# ESP32-S2-Ink.net
KiCad netlist of a schematic drawn in Altium Designer
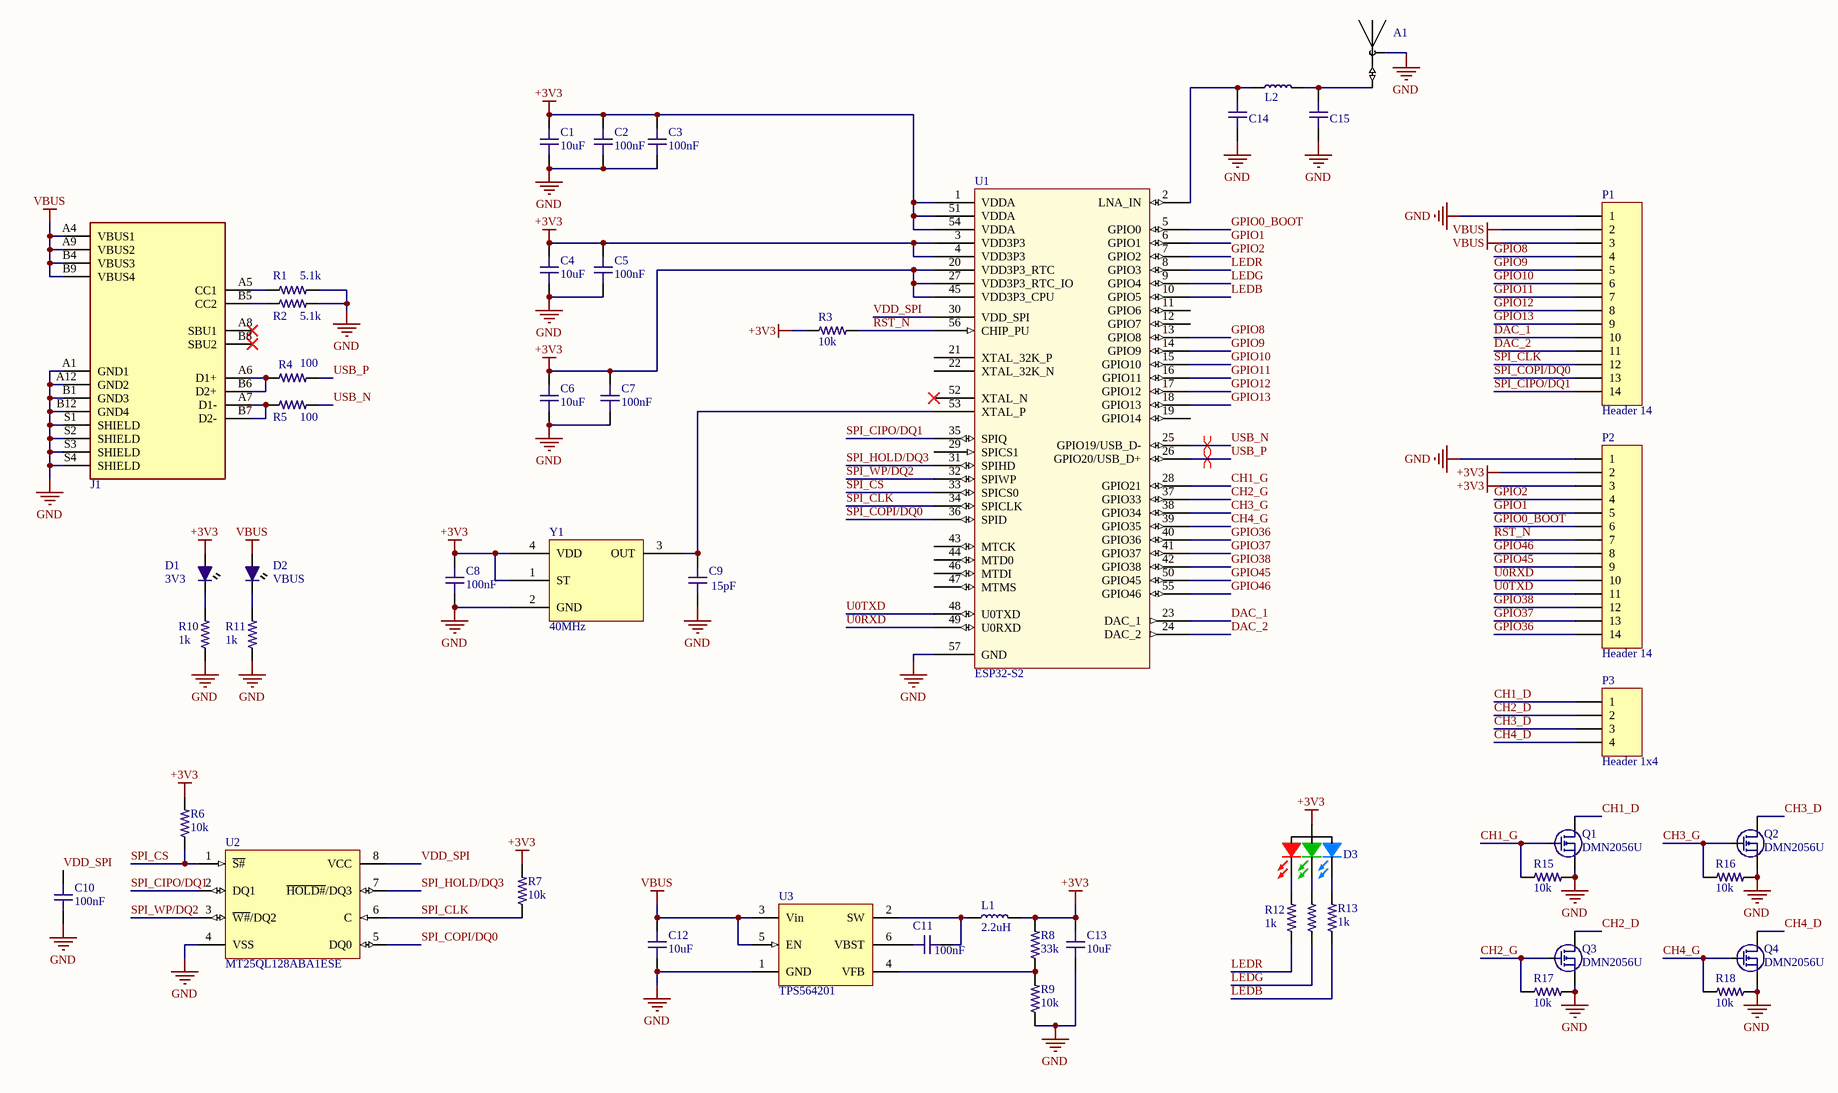
[diagram p0: ESP32-S2-Ink.SchDoc]

(export (version "E")
  (design (tool "Eeschema 10.0.6"))
  (components
    (comp (ref "A1")
      (value "0479480001")
      (footprint "0479480001")
      (description "2.4GHz Bluetooth, WLAN, Zigbee™ Chip RF Antenna 2.4GHz ~ 2.483.5GHz 3dBi Solder Surface Mount")
      (libsource (lib "RF Components") (part "Molex 0479480001"))
    )
    (comp (ref "C1")
      (value "10uF")
      (footprint "C0402-HIGH-DENSITY")
      (description "Chip Capacitor, 0402, 10uF, 10V, X5R")
      (fields (field (name "Comment") "C0402 10uF 10V"))
      (libsource (lib "Capacitors") (part "C0402 10uF 10V"))
    )
    (comp (ref "C2")
      (value "100nF")
      (footprint "C0402-HIGH-DENSITY")
      (description "Chip Capacitor, 0402, 100nF, 10V, X5R")
      (fields (field (name "Comment") "C0402 100nF 10V X5R"))
      (libsource (lib "Capacitors") (part "C0402 100nF 10V X5R"))
    )
    (comp (ref "C3")
      (value "100nF")
      (footprint "C0402-HIGH-DENSITY")
      (description "Chip Capacitor, 0402, 100nF, 10V, X5R")
      (fields (field (name "Comment") "C0402 100nF 10V X5R"))
      (libsource (lib "Capacitors") (part "C0402 100nF 10V X5R"))
    )
    (comp (ref "C4")
      (value "10uF")
      (footprint "C0402-HIGH-DENSITY")
      (description "Chip Capacitor, 0402, 10uF, 10V, X5R")
      (fields (field (name "Comment") "C0402 10uF 10V"))
      (libsource (lib "Capacitors") (part "C0402 10uF 10V"))
    )
    (comp (ref "C5")
      (value "100nF")
      (footprint "C0402-HIGH-DENSITY")
      (description "Chip Capacitor, 0402, 100nF, 10V, X5R")
      (fields (field (name "Comment") "C0402 100nF 10V X5R"))
      (libsource (lib "Capacitors") (part "C0402 100nF 10V X5R"))
    )
    (comp (ref "C6")
      (value "10uF")
      (footprint "C0402-HIGH-DENSITY")
      (description "Chip Capacitor, 0402, 10uF, 10V, X5R")
      (fields (field (name "Comment") "C0402 10uF 10V"))
      (libsource (lib "Capacitors") (part "C0402 10uF 10V"))
    )
    (comp (ref "C7")
      (value "100nF")
      (footprint "C0402-HIGH-DENSITY")
      (description "Chip Capacitor, 0402, 100nF, 10V, X5R")
      (fields (field (name "Comment") "C0402 100nF 10V X5R"))
      (libsource (lib "Capacitors") (part "C0402 100nF 10V X5R"))
    )
    (comp (ref "C8")
      (value "100nF")
      (footprint "C0402-HIGH-DENSITY")
      (description "Chip Capacitor, 0402, 100nF, 10V, X5R")
      (fields (field (name "Comment") "C0402 100nF 10V X5R"))
      (libsource (lib "Capacitors") (part "C0402 100nF 10V X5R"))
    )
    (comp (ref "C9")
      (value "15pF")
      (footprint "C0402-HIGH-DENSITY")
      (description "Chip Capacitor, 0402, 15pF, 50V, C0G")
      (fields (field (name "Comment") "C0402 15pF 50V C0G"))
      (libsource (lib "Capacitors") (part "C0402 16pF 50V C0G"))
    )
    (comp (ref "C10")
      (value "100nF")
      (footprint "C0402-HIGH-DENSITY")
      (description "Chip Capacitor, 0402, 100nF, 10V, X5R")
      (fields (field (name "Comment") "C0402 100nF 10V X5R"))
      (libsource (lib "Capacitors") (part "C0402 100nF 10V X5R"))
    )
    (comp (ref "C11")
      (value "100nF")
      (footprint "C0402-HIGH-DENSITY")
      (description "Chip Capacitor, 0402, 100nF, 10V, X5R")
      (fields (field (name "Comment") "C0402 100nF 10V X5R"))
      (libsource (lib "Capacitors") (part "C0402 100nF 10V X5R"))
    )
    (comp (ref "C12")
      (value "10uF")
      (footprint "C0402-HIGH-DENSITY")
      (description "Chip Capacitor, 0402, 10uF, 10V, X5R")
      (fields (field (name "Comment") "C0402 10uF 10V"))
      (libsource (lib "Capacitors") (part "C0402 10uF 10V"))
    )
    (comp (ref "C13")
      (value "10uF")
      (footprint "C0402-HIGH-DENSITY")
      (description "Chip Capacitor, 0402, 10uF, 10V, X5R")
      (fields (field (name "Comment") "C0402 10uF 10V"))
      (libsource (lib "Capacitors") (part "C0402 10uF 10V"))
    )
    (comp (ref "C14")
      (value "0402 Capacitor Template")
      (footprint "C0402-HIGH-DENSITY")
      (description "Chip Capacitor, 0402, ??nF, 10V, X7R")
      (libsource (lib "Capacitors") (part "0402 Capacitor Template"))
    )
    (comp (ref "C15")
      (value "0402 Capacitor Template")
      (footprint "C0402-HIGH-DENSITY")
      (description "Chip Capacitor, 0402, ??nF, 10V, X7R")
      (libsource (lib "Capacitors") (part "0402 Capacitor Template"))
    )
    (comp (ref "D1")
      (value "3V3")
      (footprint "LED0603-IPC")
      (description "LED YELLOW CLEAR 0603 SMD")
      (libsource (lib "Diodes") (part "LED 0603 Yellow"))
    )
    (comp (ref "D2")
      (value "VBUS")
      (footprint "LED0603-IPC")
      (description "LED YELLOW CLEAR 0603 SMD")
      (libsource (lib "Diodes") (part "LED 0603 Yellow"))
    )
    (comp (ref "D3")
      (value "RGB")
      (footprint "Diodes:LED_0606_RGB_WURTH")
      (description "RGB Led 1.6 x 1.6 mm Diffused")
      (fields
        (field (name "MANUFACTURER") "Everlight")
        (field (name "MANUFACTURER PART NUMBER") "19-237/R6GHBHW-C01/2T")
      )
      (libsource (lib "Diodes") (part "Led_RGB_0606"))
    )
    (comp (ref "J1")
      (value "16 Pin Mid Mount USB C")
      (footprint "USB-C - 16 Pin Mid Mount")
      (description "USB-C USB 2.0 5A PD 16 Position Mid Mount")
      (fields (field (name "MANUFACTURER") "Jing Extension of the Electronic Co"))
      (libsource (lib "Connectors") (part "USB C USB 2.0 and PD"))
    )
    (comp (ref "L1")
      (value "2.2uH")
      (footprint "L1008")
      (description "2.2µH Shielded Inductor 2.05A 117mOhm Max 1008 (2520 Metric)")
      (fields (field (name "Comment") "SDEM25201B-2R2MS"))
      (libsource (lib "Inductors") (part "SDEM25201B-2R2MS"))
    )
    (comp (ref "L2")
      (value "! Inductor Template")
      (footprint "L0402-Murata-WW-High-Density")
      (description "Inductor, ??uH")
      (libsource (lib "Inductors") (part "! Inductor Template"))
    )
    (comp (ref "P1")
      (value "Header 14")
      (footprint "HDR1X14")
      (description "Header, 14-Pin")
      (fields (field (name "PUBLISHER") "Altium Limited"))
      (libsource (lib "Miscellaneous Connectors") (part "Header 14"))
    )
    (comp (ref "P2")
      (value "Header 14")
      (footprint "HDR1X14")
      (description "Header, 14-Pin")
      (fields (field (name "PUBLISHER") "Altium Limited"))
      (libsource (lib "Miscellaneous Connectors") (part "Header 14"))
    )
    (comp (ref "P3")
      (value "Header 1x4")
      (footprint "HEADER 1X4 SMD 2.54mm")
      (description "Header, 4-Pin")
      (fields (field (name "PUBLISHER") "Altium Limited"))
      (libsource (lib "Connectors") (part "Header 1x4"))
    )
    (comp (ref "Q1")
      (value "DMN2056U")
      (footprint "SOT23-DMN2056")
      (description "MOSFET N-Ch -20V VDSS Enchanced Mosfet 4.2A")
      (libsource (lib "Transistors") (part "DMN2056U"))
    )
    (comp (ref "Q2")
      (value "DMN2056U")
      (footprint "SOT23-DMN2056")
      (description "MOSFET N-Ch -20V VDSS Enchanced Mosfet 4.2A")
      (libsource (lib "Transistors") (part "DMN2056U"))
    )
    (comp (ref "Q3")
      (value "DMN2056U")
      (footprint "SOT23-DMN2056")
      (description "MOSFET N-Ch -20V VDSS Enchanced Mosfet 4.2A")
      (libsource (lib "Transistors") (part "DMN2056U"))
    )
    (comp (ref "Q4")
      (value "DMN2056U")
      (footprint "SOT23-DMN2056")
      (description "MOSFET N-Ch -20V VDSS Enchanced Mosfet 4.2A")
      (libsource (lib "Transistors") (part "DMN2056U"))
    )
    (comp (ref "R1")
      (value "5.1k")
      (footprint "R0402-HIGH-DENSITY")
      (description "RES SMD 5.1K OHM 1% 1/10W 0402")
      (fields (field (name "Comment") "R0402 5.1K 1%"))
      (libsource (lib "Resistors") (part "R0402 5.1K 1%"))
    )
    (comp (ref "R2")
      (value "5.1k")
      (footprint "R0402-HIGH-DENSITY")
      (description "RES SMD 5.1K OHM 1% 1/10W 0402")
      (fields (field (name "Comment") "R0402 5.1K 1%"))
      (libsource (lib "Resistors") (part "R0402 5.1K 1%"))
    )
    (comp (ref "R3")
      (value "10k")
      (footprint "R0402-HIGH-DENSITY")
      (description "Chip Resistor, 0402, 10k ohms, 1%, 1/16 W")
      (fields (field (name "Comment") "R0402 10k 1%"))
      (libsource (lib "Resistors") (part "R0402 10k 1%"))
    )
    (comp (ref "R4")
      (value "100")
      (footprint "R0402-HIGH-DENSITY")
      (description "Chip Resistor, 0402, 100 ohms, 1%, 1/16 W")
      (fields (field (name "Comment") "R0402 100R 1%"))
      (libsource (lib "Resistors") (part "R0402 100R 1%"))
    )
    (comp (ref "R5")
      (value "100")
      (footprint "R0402-HIGH-DENSITY")
      (description "Chip Resistor, 0402, 100 ohms, 1%, 1/16 W")
      (fields (field (name "Comment") "R0402 100R 1%"))
      (libsource (lib "Resistors") (part "R0402 100R 1%"))
    )
    (comp (ref "R6")
      (value "10k")
      (footprint "R0402-HIGH-DENSITY")
      (description "Chip Resistor, 0402, 10k ohms, 1%, 1/16 W")
      (fields (field (name "Comment") "R0402 10k 1%"))
      (libsource (lib "Resistors") (part "R0402 10k 1%"))
    )
    (comp (ref "R7")
      (value "10k")
      (footprint "R0402-HIGH-DENSITY")
      (description "Chip Resistor, 0402, 10k ohms, 1%, 1/16 W")
      (fields (field (name "Comment") "R0402 10k 1%"))
      (libsource (lib "Resistors") (part "R0402 10k 1%"))
    )
    (comp (ref "R8")
      (value "33k")
      (footprint "R0402-HIGH-DENSITY")
      (description "Chip Resistor, 0402, 33k ohms, 1%, 1/16 W")
      (fields (field (name "Comment") "R0402 33k 1%"))
      (libsource (lib "Resistors") (part "R0402 33k 1%"))
    )
    (comp (ref "R9")
      (value "10k")
      (footprint "R0402-HIGH-DENSITY")
      (description "Chip Resistor, 0402, 10k ohms, 1%, 1/16 W")
      (fields (field (name "Comment") "R0402 10k 1%"))
      (libsource (lib "Resistors") (part "R0402 10k 1%"))
    )
    (comp (ref "R10")
      (value "1k")
      (footprint "R0402-HIGH-DENSITY")
      (description "Chip Resistor, 0402, 1k ohms, 1%, 1/16 W")
      (fields (field (name "Comment") "R0402 1k 1%"))
      (libsource (lib "Resistors") (part "R0402 1k 1%"))
    )
    (comp (ref "R11")
      (value "1k")
      (footprint "R0402-HIGH-DENSITY")
      (description "Chip Resistor, 0402, 1k ohms, 1%, 1/16 W")
      (fields (field (name "Comment") "R0402 1k 1%"))
      (libsource (lib "Resistors") (part "R0402 1k 1%"))
    )
    (comp (ref "R12")
      (value "1k")
      (footprint "R0402-HIGH-DENSITY")
      (description "Chip Resistor, 0402, 1k ohms, 1%, 1/16 W")
      (fields (field (name "Comment") "R0402 1k 1%"))
      (libsource (lib "Resistors") (part "R0402 1k 1%"))
    )
    (comp (ref "R13")
      (value "1k")
      (footprint "R0402-HIGH-DENSITY")
      (description "Chip Resistor, 0402, 1k ohms, 1%, 1/16 W")
      (fields (field (name "Comment") "R0402 1k 1%"))
      (libsource (lib "Resistors") (part "R0402 1k 1%"))
    )
    (comp (ref "R14")
      (value "R0402 1k 1%")
      (footprint "R0402-HIGH-DENSITY")
      (description "Chip Resistor, 0402, 1k ohms, 1%, 1/16 W")
      (libsource (lib "Resistors") (part "R0402 1k 1%"))
    )
    (comp (ref "R15")
      (value "10k")
      (footprint "R0402-HIGH-DENSITY")
      (description "Chip Resistor, 0402, 10k ohms, 1%, 1/16 W")
      (fields (field (name "Comment") "R0402 10k 1%"))
      (libsource (lib "Resistors") (part "R0402 10k 1%"))
    )
    (comp (ref "R16")
      (value "10k")
      (footprint "R0402-HIGH-DENSITY")
      (description "Chip Resistor, 0402, 10k ohms, 1%, 1/16 W")
      (fields (field (name "Comment") "R0402 10k 1%"))
      (libsource (lib "Resistors") (part "R0402 10k 1%"))
    )
    (comp (ref "R17")
      (value "10k")
      (footprint "R0402-HIGH-DENSITY")
      (description "Chip Resistor, 0402, 10k ohms, 1%, 1/16 W")
      (fields (field (name "Comment") "R0402 10k 1%"))
      (libsource (lib "Resistors") (part "R0402 10k 1%"))
    )
    (comp (ref "R18")
      (value "10k")
      (footprint "R0402-HIGH-DENSITY")
      (description "Chip Resistor, 0402, 10k ohms, 1%, 1/16 W")
      (fields (field (name "Comment") "R0402 10k 1%"))
      (libsource (lib "Resistors") (part "R0402 10k 1%"))
    )
    (comp (ref "U1")
      (value "ESP32-S2")
      (footprint "QFN56")
      (description "WiFi 802.11b/g/n Transceiver Module 2.4GHz QFN-56")
      (libsource (lib "Integrated Circuits") (part "ESP32-S2"))
    )
    (comp (ref "U2")
      (value "MT25QL128ABA1ESE")
      (footprint "SOIC127P800X216-8N")
      (description "SPI Flash, 128Mb, 3V")
      (libsource (lib "Integrated Circuits") (part "MT25QL128ABA1ESE"))
    )
    (comp (ref "U3")
      (value "TPS564201")
      (footprint "SOT95P280X90-6N")
      (description "Buck Converter, 4.5-17V in, 0.76-7V out, 4A, TSOT-6")
      (fields
        (field (name "MANUFACTURER") "Texas Instruments")
        (field (name "LAST MODIFIED BY") "Peter Kazakoff")
      )
      (libsource (lib "Integrated Circuits") (part "TPS564201"))
    )
    (comp (ref "Y1")
      (value "40MHz")
      (footprint "SiT8008B")
      (description "OSC MEMS 40.0000MHZ 1.8-3.3V 2016 SMD 15pF Load")
      (libsource (lib "RF Components") (part "40MHZ CMOS ±10ppm"))
    )
  )
  (nets
    (net (code "1") (name "+3V3") (class "Default")
      (node (ref "C1") (pin "2") (pintype "passive"))
      (node (ref "C13") (pin "2") (pintype "passive"))
      (node (ref "C2") (pin "2") (pintype "passive"))
      (node (ref "C3") (pin "2") (pintype "passive"))
      (node (ref "C4") (pin "2") (pintype "passive"))
      (node (ref "C5") (pin "2") (pintype "passive"))
      (node (ref "C6") (pin "2") (pintype "passive"))
      (node (ref "C7") (pin "2") (pintype "passive"))
      (node (ref "C8") (pin "2") (pintype "passive"))
      (node (ref "D1") (pin "A") (pintype "passive"))
      (node (ref "D3") (pin "A") (pinfunction "A_A") (pintype "passive"))
      (node (ref "L1") (pin "2") (pintype "passive"))
      (node (ref "P2") (pin "2") (pinfunction "2_2") (pintype "passive"))
      (node (ref "P2") (pin "3") (pinfunction "3_3") (pintype "passive"))
      (node (ref "R3") (pin "1") (pintype "passive"))
      (node (ref "R6") (pin "1") (pintype "passive"))
      (node (ref "R7") (pin "1") (pintype "passive"))
      (node (ref "R8") (pin "2") (pintype "passive"))
      (node (ref "U1") (pin "1") (pinfunction "VDDA_1") (pintype "power_in"))
      (node (ref "U1") (pin "20") (pinfunction "VDD3P3_RTC_20") (pintype "power_in"))
      (node (ref "U1") (pin "27") (pinfunction "VDD3P3_RTC_IO_27") (pintype "power_in"))
      (node (ref "U1") (pin "3") (pinfunction "VDD3P3_3") (pintype "power_in"))
      (node (ref "U1") (pin "4") (pinfunction "VDD3P3_4") (pintype "power_in"))
      (node (ref "U1") (pin "45") (pinfunction "VDD3P3_CPU_45") (pintype "power_in"))
      (node (ref "U1") (pin "51") (pinfunction "VDDA_51") (pintype "power_in"))
      (node (ref "U1") (pin "54") (pinfunction "VDDA_54") (pintype "power_in"))
      (node (ref "Y1") (pin "1") (pinfunction "ST_1") (pintype "passive"))
      (node (ref "Y1") (pin "4") (pinfunction "VDD_4") (pintype "passive"))
    )
    (net (code "2") (name "/CH1_D") (class "Default")
      (node (ref "P3") (pin "1") (pinfunction "1_1") (pintype "passive"))
      (node (ref "Q1") (pin "3") (pinfunction "D_3") (pintype "passive"))
    )
    (net (code "3") (name "/CH1_G") (class "Default")
      (node (ref "Q1") (pin "1") (pinfunction "G_1") (pintype "passive"))
      (node (ref "R15") (pin "2") (pintype "passive"))
      (node (ref "U1") (pin "28") (pinfunction "GPIO21_28") (pintype "bidirectional"))
    )
    (net (code "4") (name "/CH2_D") (class "Default")
      (node (ref "P3") (pin "2") (pinfunction "2_2") (pintype "passive"))
      (node (ref "Q3") (pin "3") (pinfunction "D_3") (pintype "passive"))
    )
    (net (code "5") (name "/CH2_G") (class "Default")
      (node (ref "Q3") (pin "1") (pinfunction "G_1") (pintype "passive"))
      (node (ref "R17") (pin "2") (pintype "passive"))
      (node (ref "U1") (pin "37") (pinfunction "GPIO33_37") (pintype "bidirectional"))
    )
    (net (code "6") (name "/CH3_D") (class "Default")
      (node (ref "P3") (pin "3") (pinfunction "3_3") (pintype "passive"))
      (node (ref "Q2") (pin "3") (pinfunction "D_3") (pintype "passive"))
    )
    (net (code "7") (name "/CH3_G") (class "Default")
      (node (ref "Q2") (pin "1") (pinfunction "G_1") (pintype "passive"))
      (node (ref "R16") (pin "2") (pintype "passive"))
      (node (ref "U1") (pin "38") (pinfunction "GPIO34_38") (pintype "bidirectional"))
    )
    (net (code "8") (name "/CH4_D") (class "Default")
      (node (ref "P3") (pin "4") (pinfunction "4_4") (pintype "passive"))
      (node (ref "Q4") (pin "3") (pinfunction "D_3") (pintype "passive"))
    )
    (net (code "9") (name "/CH4_G") (class "Default")
      (node (ref "Q4") (pin "1") (pinfunction "G_1") (pintype "passive"))
      (node (ref "R18") (pin "2") (pintype "passive"))
      (node (ref "U1") (pin "39") (pinfunction "GPIO35_39") (pintype "bidirectional"))
    )
    (net (code "10") (name "/DAC_1") (class "Default")
      (node (ref "P1") (pin "10") (pinfunction "10_10") (pintype "passive"))
      (node (ref "U1") (pin "23") (pinfunction "DAC_1_23") (pintype "output"))
    )
    (net (code "11") (name "/DAC_2") (class "Default")
      (node (ref "P1") (pin "11") (pinfunction "11_11") (pintype "passive"))
      (node (ref "U1") (pin "24") (pinfunction "DAC_2_24") (pintype "output"))
    )
    (net (code "12") (name "/GPIO0_BOOT") (class "Default")
      (node (ref "P2") (pin "6") (pinfunction "6_6") (pintype "passive"))
      (node (ref "U1") (pin "5") (pinfunction "GPIO0_5") (pintype "bidirectional"))
    )
    (net (code "13") (name "/GPIO1") (class "Default")
      (node (ref "P2") (pin "5") (pinfunction "5_5") (pintype "passive"))
      (node (ref "U1") (pin "6") (pinfunction "GPIO1_6") (pintype "bidirectional"))
    )
    (net (code "14") (name "/GPIO2") (class "Default")
      (node (ref "P2") (pin "4") (pinfunction "4_4") (pintype "passive"))
      (node (ref "U1") (pin "7") (pinfunction "GPIO2_7") (pintype "bidirectional"))
    )
    (net (code "15") (name "/GPIO8") (class "Default")
      (node (ref "P1") (pin "4") (pinfunction "4_4") (pintype "passive"))
      (node (ref "U1") (pin "13") (pinfunction "GPIO8_13") (pintype "bidirectional"))
    )
    (net (code "16") (name "/GPIO9") (class "Default")
      (node (ref "P1") (pin "5") (pinfunction "5_5") (pintype "passive"))
      (node (ref "U1") (pin "14") (pinfunction "GPIO9_14") (pintype "bidirectional"))
    )
    (net (code "17") (name "/GPIO10") (class "Default")
      (node (ref "P1") (pin "6") (pinfunction "6_6") (pintype "passive"))
      (node (ref "U1") (pin "15") (pinfunction "GPIO10_15") (pintype "bidirectional"))
    )
    (net (code "18") (name "/GPIO11") (class "Default")
      (node (ref "P1") (pin "7") (pinfunction "7_7") (pintype "passive"))
      (node (ref "U1") (pin "16") (pinfunction "GPIO11_16") (pintype "bidirectional"))
    )
    (net (code "19") (name "/GPIO12") (class "Default")
      (node (ref "P1") (pin "8") (pinfunction "8_8") (pintype "passive"))
      (node (ref "U1") (pin "17") (pinfunction "GPIO12_17") (pintype "bidirectional"))
    )
    (net (code "20") (name "/GPIO13") (class "Default")
      (node (ref "P1") (pin "9") (pinfunction "9_9") (pintype "passive"))
      (node (ref "U1") (pin "18") (pinfunction "GPIO13_18") (pintype "bidirectional"))
    )
    (net (code "21") (name "/GPIO36") (class "Default")
      (node (ref "P2") (pin "14") (pinfunction "14_14") (pintype "passive"))
      (node (ref "U1") (pin "40") (pinfunction "GPIO36_40") (pintype "bidirectional"))
    )
    (net (code "22") (name "/GPIO37") (class "Default")
      (node (ref "P2") (pin "13") (pinfunction "13_13") (pintype "passive"))
      (node (ref "U1") (pin "41") (pinfunction "GPIO37_41") (pintype "bidirectional"))
    )
    (net (code "23") (name "/GPIO38") (class "Default")
      (node (ref "P2") (pin "12") (pinfunction "12_12") (pintype "passive"))
      (node (ref "U1") (pin "42") (pinfunction "GPIO38_42") (pintype "bidirectional"))
    )
    (net (code "24") (name "/GPIO45") (class "Default")
      (node (ref "P2") (pin "9") (pinfunction "9_9") (pintype "passive"))
      (node (ref "U1") (pin "50") (pinfunction "GPIO45_50") (pintype "bidirectional"))
    )
    (net (code "25") (name "/GPIO46") (class "Default")
      (node (ref "P2") (pin "8") (pinfunction "8_8") (pintype "passive"))
      (node (ref "U1") (pin "55") (pinfunction "GPIO46_55") (pintype "bidirectional"))
    )
    (net (code "26") (name "/LEDB") (class "Default")
      (node (ref "R13") (pin "1") (pintype "passive"))
      (node (ref "U1") (pin "10") (pinfunction "GPIO5_10") (pintype "bidirectional"))
    )
    (net (code "27") (name "/LEDG") (class "Default")
      (node (ref "R14") (pin "1") (pintype "passive"))
      (node (ref "U1") (pin "9") (pinfunction "GPIO4_9") (pintype "bidirectional"))
    )
    (net (code "28") (name "/LEDR") (class "Default")
      (node (ref "R12") (pin "1") (pintype "passive"))
      (node (ref "U1") (pin "8") (pinfunction "GPIO3_8") (pintype "bidirectional"))
    )
    (net (code "29") (name "/RST_N") (class "Default")
      (node (ref "P2") (pin "7") (pinfunction "7_7") (pintype "passive"))
      (node (ref "R3") (pin "2") (pintype "passive"))
      (node (ref "U1") (pin "56") (pinfunction "CHIP_PU_56") (pintype "input"))
    )
    (net (code "30") (name "/SPI_CIPO{slash}DQ1") (class "Default")
      (node (ref "P1") (pin "14") (pinfunction "14_14") (pintype "passive"))
      (node (ref "U1") (pin "35") (pinfunction "SPIQ_35") (pintype "bidirectional"))
      (node (ref "U2") (pin "2") (pinfunction "DQ1_2") (pintype "bidirectional"))
    )
    (net (code "31") (name "/SPI_CLK") (class "Default")
      (node (ref "P1") (pin "12") (pinfunction "12_12") (pintype "passive"))
      (node (ref "R7") (pin "2") (pintype "passive"))
      (node (ref "U1") (pin "34") (pinfunction "SPICLK_34") (pintype "bidirectional"))
      (node (ref "U2") (pin "6") (pinfunction "C_6") (pintype "input"))
    )
    (net (code "32") (name "/SPI_COPI{slash}DQ0") (class "Default")
      (node (ref "P1") (pin "13") (pinfunction "13_13") (pintype "passive"))
      (node (ref "U1") (pin "36") (pinfunction "SPID_36") (pintype "bidirectional"))
      (node (ref "U2") (pin "5") (pinfunction "DQ0_5") (pintype "bidirectional"))
    )
    (net (code "33") (name "/SPI_CS") (class "Default")
      (node (ref "R6") (pin "2") (pintype "passive"))
      (node (ref "U1") (pin "33") (pinfunction "SPICS0_33") (pintype "bidirectional"))
      (node (ref "U2") (pin "1") (pinfunction "~{S#}_1") (pintype "input"))
    )
    (net (code "34") (name "/SPI_HOLD{slash}DQ3") (class "Default")
      (node (ref "U1") (pin "31") (pinfunction "SPIHD_31") (pintype "bidirectional"))
      (node (ref "U2") (pin "7") (pinfunction "~{HOLD#}/DQ3_7") (pintype "bidirectional"))
    )
    (net (code "35") (name "/SPI_WP{slash}DQ2") (class "Default")
      (node (ref "U1") (pin "32") (pinfunction "SPIWP_32") (pintype "bidirectional"))
      (node (ref "U2") (pin "3") (pinfunction "~{W#}/DQ2_3") (pintype "bidirectional"))
    )
    (net (code "36") (name "/U0RXD") (class "Default")
      (node (ref "P2") (pin "10") (pinfunction "10_10") (pintype "passive"))
      (node (ref "U1") (pin "49") (pinfunction "U0RXD_49") (pintype "bidirectional"))
    )
    (net (code "37") (name "/U0TXD") (class "Default")
      (node (ref "P2") (pin "11") (pinfunction "11_11") (pintype "passive"))
      (node (ref "U1") (pin "48") (pinfunction "U0TXD_48") (pintype "bidirectional"))
    )
    (net (code "38") (name "/USB_N") (class "Default")
      (node (ref "R5") (pin "2") (pintype "passive"))
      (node (ref "U1") (pin "25") (pinfunction "GPIO19/USB_D-_25") (pintype "bidirectional"))
    )
    (net (code "39") (name "/USB_P") (class "Default")
      (node (ref "R4") (pin "2") (pintype "passive"))
      (node (ref "U1") (pin "26") (pinfunction "GPIO20/USB_D+_26") (pintype "bidirectional"))
    )
    (net (code "40") (name "/VDD_SPI") (class "Default")
      (node (ref "C10") (pin "2") (pintype "passive"))
      (node (ref "U1") (pin "30") (pinfunction "VDD_SPI_30") (pintype "power_in"))
      (node (ref "U2") (pin "8") (pinfunction "VCC_8") (pintype "power_in"))
    )
    (net (code "41") (name "GND") (class "Default")
      (node (ref "A1") (pin "2") (pinfunction "2_2") (pintype "power_in"))
      (node (ref "C1") (pin "1") (pintype "passive"))
      (node (ref "C10") (pin "1") (pintype "passive"))
      (node (ref "C12") (pin "1") (pintype "passive"))
      (node (ref "C13") (pin "1") (pintype "passive"))
      (node (ref "C14") (pin "1") (pintype "passive"))
      (node (ref "C15") (pin "1") (pintype "passive"))
      (node (ref "C2") (pin "1") (pintype "passive"))
      (node (ref "C3") (pin "1") (pintype "passive"))
      (node (ref "C4") (pin "1") (pintype "passive"))
      (node (ref "C5") (pin "1") (pintype "passive"))
      (node (ref "C6") (pin "1") (pintype "passive"))
      (node (ref "C7") (pin "1") (pintype "passive"))
      (node (ref "C8") (pin "1") (pintype "passive"))
      (node (ref "C9") (pin "1") (pintype "passive"))
      (node (ref "J1") (pin "A1") (pinfunction "GND1_A1") (pintype "passive"))
      (node (ref "J1") (pin "A12") (pinfunction "GND2_A12") (pintype "passive"))
      (node (ref "J1") (pin "B1") (pinfunction "GND3_B1") (pintype "passive"))
      (node (ref "J1") (pin "B12") (pinfunction "GND4_B12") (pintype "passive"))
      (node (ref "J1") (pin "S1") (pinfunction "SHIELD_S1") (pintype "passive"))
      (node (ref "J1") (pin "S2") (pinfunction "SHIELD_S2") (pintype "passive"))
      (node (ref "J1") (pin "S3") (pinfunction "SHIELD_S3") (pintype "passive"))
      (node (ref "J1") (pin "S4") (pinfunction "SHIELD_S4") (pintype "passive"))
      (node (ref "P1") (pin "1") (pinfunction "1_1") (pintype "passive"))
      (node (ref "P2") (pin "1") (pinfunction "1_1") (pintype "passive"))
      (node (ref "Q1") (pin "2") (pinfunction "S_2") (pintype "passive"))
      (node (ref "Q2") (pin "2") (pinfunction "S_2") (pintype "passive"))
      (node (ref "Q3") (pin "2") (pinfunction "S_2") (pintype "passive"))
      (node (ref "Q4") (pin "2") (pinfunction "S_2") (pintype "passive"))
      (node (ref "R1") (pin "2") (pintype "passive"))
      (node (ref "R10") (pin "1") (pintype "passive"))
      (node (ref "R11") (pin "1") (pintype "passive"))
      (node (ref "R15") (pin "1") (pintype "passive"))
      (node (ref "R16") (pin "1") (pintype "passive"))
      (node (ref "R17") (pin "1") (pintype "passive"))
      (node (ref "R18") (pin "1") (pintype "passive"))
      (node (ref "R2") (pin "2") (pintype "passive"))
      (node (ref "R9") (pin "1") (pintype "passive"))
      (node (ref "U1") (pin "57") (pinfunction "GND_57") (pintype "power_in"))
      (node (ref "U2") (pin "4") (pinfunction "VSS_4") (pintype "power_in"))
      (node (ref "U3") (pin "1") (pinfunction "GND_1") (pintype "power_in"))
      (node (ref "Y1") (pin "2") (pinfunction "GND_2") (pintype "passive"))
    )
    (net (code "42") (name "Net-(A1-FEED)") (class "Default")
      (node (ref "A1") (pin "1") (pinfunction "FEED_1") (pintype "bidirectional"))
      (node (ref "C15") (pin "2") (pintype "passive"))
      (node (ref "L2") (pin "2") (pintype "passive"))
    )
    (net (code "43") (name "Net-(D1-PadK)") (class "Default")
      (node (ref "D1") (pin "K") (pintype "passive"))
      (node (ref "R10") (pin "2") (pintype "passive"))
    )
    (net (code "44") (name "Net-(D2-PadK)") (class "Default")
      (node (ref "D2") (pin "K") (pintype "passive"))
      (node (ref "R11") (pin "2") (pintype "passive"))
    )
    (net (code "45") (name "Net-(D3-PadBK)") (class "Default")
      (node (ref "D3") (pin "BK") (pinfunction "BK_BK") (pintype "passive"))
      (node (ref "R13") (pin "2") (pintype "passive"))
    )
    (net (code "46") (name "Net-(D3-PadGK)") (class "Default")
      (node (ref "D3") (pin "GK") (pinfunction "GK_GK") (pintype "passive"))
      (node (ref "R14") (pin "2") (pintype "passive"))
    )
    (net (code "47") (name "Net-(D3-PadRK)") (class "Default")
      (node (ref "D3") (pin "RK") (pinfunction "RK_RK") (pintype "passive"))
      (node (ref "R12") (pin "2") (pintype "passive"))
    )
    (net (code "48") (name "Net-(J1-CC1)") (class "Default")
      (node (ref "J1") (pin "A5") (pinfunction "CC1_A5") (pintype "passive"))
      (node (ref "R1") (pin "1") (pintype "passive"))
    )
    (net (code "49") (name "Net-(J1-CC2)") (class "Default")
      (node (ref "J1") (pin "B5") (pinfunction "CC2_B5") (pintype "passive"))
      (node (ref "R2") (pin "1") (pintype "passive"))
    )
    (net (code "50") (name "Net-(J1-D1+)") (class "Default")
      (node (ref "J1") (pin "A6") (pinfunction "D1+_A6") (pintype "passive"))
      (node (ref "J1") (pin "B6") (pinfunction "D2+_B6") (pintype "passive"))
      (node (ref "R4") (pin "1") (pintype "passive"))
    )
    (net (code "51") (name "Net-(J1-D1-)") (class "Default")
      (node (ref "J1") (pin "A7") (pinfunction "D1-_A7") (pintype "passive"))
      (node (ref "J1") (pin "B7") (pinfunction "D2-_B7") (pintype "passive"))
      (node (ref "R5") (pin "1") (pintype "passive"))
    )
    (net (code "52") (name "Net-(U1-LNA_IN)") (class "Default")
      (node (ref "C14") (pin "2") (pintype "passive"))
      (node (ref "L2") (pin "1") (pintype "passive"))
      (node (ref "U1") (pin "2") (pinfunction "LNA_IN_2") (pintype "bidirectional"))
    )
    (net (code "53") (name "Net-(U1-XTAL_P)") (class "Default")
      (node (ref "C9") (pin "2") (pintype "passive"))
      (node (ref "U1") (pin "53") (pinfunction "XTAL_P_53") (pintype "passive"))
      (node (ref "Y1") (pin "3") (pinfunction "OUT_3") (pintype "passive"))
    )
    (net (code "54") (name "Net-(U3-SW)") (class "Default")
      (node (ref "C11") (pin "1") (pintype "passive"))
      (node (ref "L1") (pin "1") (pintype "passive"))
      (node (ref "U3") (pin "2") (pinfunction "SW_2") (pintype "passive"))
    )
    (net (code "55") (name "Net-(U3-VBST)") (class "Default")
      (node (ref "C11") (pin "2") (pintype "passive"))
      (node (ref "U3") (pin "6") (pinfunction "VBST_6") (pintype "passive"))
    )
    (net (code "56") (name "Net-(U3-VFB)") (class "Default")
      (node (ref "R8") (pin "1") (pintype "passive"))
      (node (ref "R9") (pin "2") (pintype "passive"))
      (node (ref "U3") (pin "4") (pinfunction "VFB_4") (pintype "passive"))
    )
    (net (code "57") (name "VBUS") (class "Default")
      (node (ref "C12") (pin "2") (pintype "passive"))
      (node (ref "D2") (pin "A") (pintype "passive"))
      (node (ref "J1") (pin "A4") (pinfunction "VBUS1_A4") (pintype "passive"))
      (node (ref "J1") (pin "A9") (pinfunction "VBUS2_A9") (pintype "passive"))
      (node (ref "J1") (pin "B4") (pinfunction "VBUS3_B4") (pintype "passive"))
      (node (ref "J1") (pin "B9") (pinfunction "VBUS4_B9") (pintype "passive"))
      (node (ref "P1") (pin "2") (pinfunction "2_2") (pintype "passive"))
      (node (ref "P1") (pin "3") (pinfunction "3_3") (pintype "passive"))
      (node (ref "U3") (pin "3") (pinfunction "Vin_3") (pintype "power_in"))
      (node (ref "U3") (pin "5") (pinfunction "EN_5") (pintype "input"))
    )
    (net (code "58") (name "unconnected-(J1-SBU1-PadA8)") (class "Default")
      (node (ref "J1") (pin "A8") (pinfunction "SBU1_A8") (pintype "passive+no_connect"))
    )
    (net (code "59") (name "unconnected-(J1-SBU2-PadB8)") (class "Default")
      (node (ref "J1") (pin "B8") (pinfunction "SBU2_B8") (pintype "passive+no_connect"))
    )
    (net (code "60") (name "unconnected-(U1-GPIO6-Pad11)") (class "Default")
      (node (ref "U1") (pin "11") (pinfunction "GPIO6_11") (pintype "bidirectional"))
    )
    (net (code "61") (name "unconnected-(U1-GPIO7-Pad12)") (class "Default")
      (node (ref "U1") (pin "12") (pinfunction "GPIO7_12") (pintype "bidirectional"))
    )
    (net (code "62") (name "unconnected-(U1-GPIO14-Pad19)") (class "Default")
      (node (ref "U1") (pin "19") (pinfunction "GPIO14_19") (pintype "bidirectional"))
    )
    (net (code "63") (name "unconnected-(U1-MTCK-Pad43)") (class "Default")
      (node (ref "U1") (pin "43") (pinfunction "MTCK_43") (pintype "bidirectional"))
    )
    (net (code "64") (name "unconnected-(U1-MTD0-Pad44)") (class "Default")
      (node (ref "U1") (pin "44") (pinfunction "MTD0_44") (pintype "bidirectional"))
    )
    (net (code "65") (name "unconnected-(U1-MTDI-Pad46)") (class "Default")
      (node (ref "U1") (pin "46") (pinfunction "MTDI_46") (pintype "bidirectional"))
    )
    (net (code "66") (name "unconnected-(U1-MTMS-Pad47)") (class "Default")
      (node (ref "U1") (pin "47") (pinfunction "MTMS_47") (pintype "bidirectional"))
    )
    (net (code "67") (name "unconnected-(U1-SPICS1-Pad29)") (class "Default")
      (node (ref "U1") (pin "29") (pinfunction "SPICS1_29") (pintype "input"))
    )
    (net (code "68") (name "unconnected-(U1-XTAL_32K_N-Pad22)") (class "Default")
      (node (ref "U1") (pin "22") (pinfunction "XTAL_32K_N_22") (pintype "passive"))
    )
    (net (code "69") (name "unconnected-(U1-XTAL_32K_P-Pad21)") (class "Default")
      (node (ref "U1") (pin "21") (pinfunction "XTAL_32K_P_21") (pintype "passive"))
    )
    (net (code "70") (name "unconnected-(U1-XTAL_N-Pad52)") (class "Default")
      (node (ref "U1") (pin "52") (pinfunction "XTAL_N_52") (pintype "passive+no_connect"))
    )
  )
)
